# RBR-RAMON.net
KiCad netlist of a schematic drawn in Altium Designer
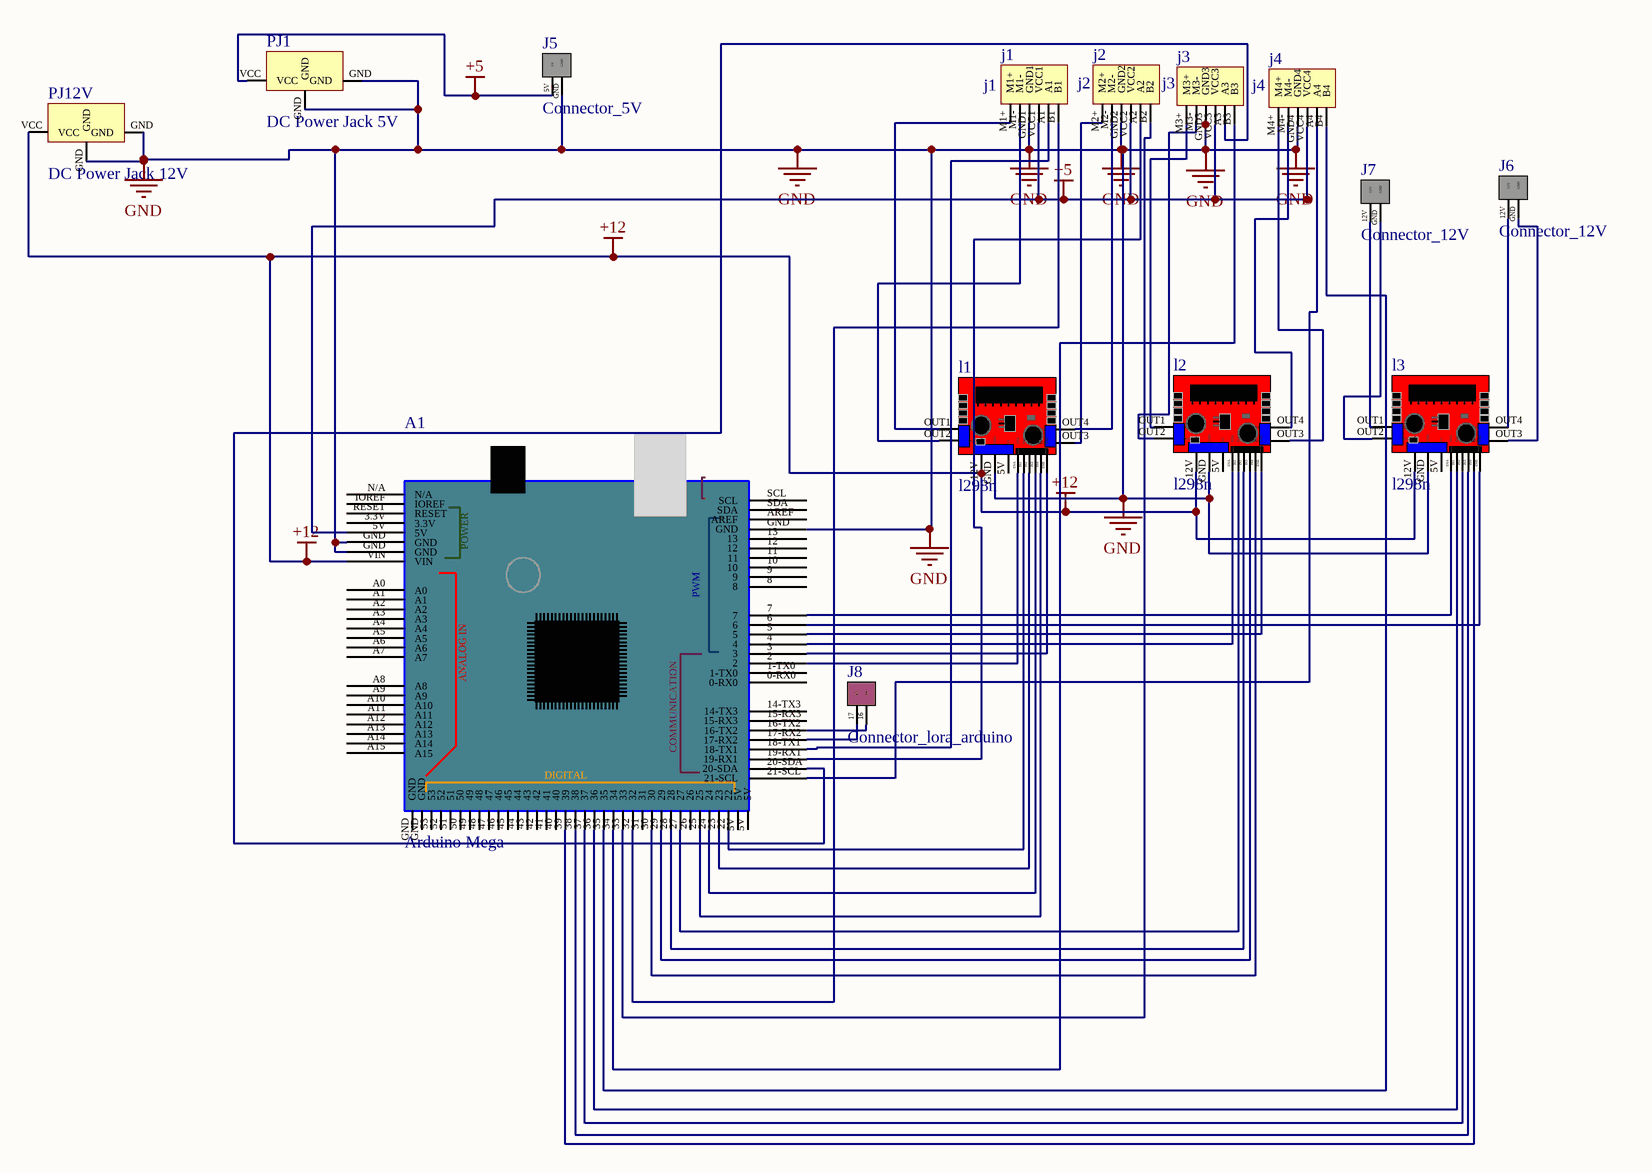
[diagram p0: RBR-RAMON.SchDoc]

(export (version "E")
  (design (tool "Eeschema 10.0.6"))
  (components
    (comp (ref "A1")
      (value "Arduino Mega")
      (footprint "Arduino Mega")
      (libsource (lib "RBR-RAMON") (part "Arduino Mega"))
    )
    (comp (ref "j1")
      (value "j1")
      (footprint "CONECTOR JST M1")
      (libsource (lib "RBR-RAMON") (part "CONECTOR JST M1"))
    )
    (comp (ref "j2")
      (value "j2")
      (footprint "CONECTOR JST M2")
      (libsource (lib "RBR-RAMON") (part "CONECTOR JST M2"))
    )
    (comp (ref "j3")
      (value "j3")
      (footprint "CONECTOR JST M3")
      (libsource (lib "RBR-RAMON") (part "CONECTOR JST M3"))
    )
    (comp (ref "j4")
      (value "j4")
      (footprint "CONECTOR JST M4")
      (libsource (lib "RBR-RAMON") (part "CONECTOR JST M4"))
    )
    (comp (ref "J5")
      (value "Connector_5V")
      (footprint "Conector_5V")
      (libsource (lib "RBR-RAMON") (part "Connector_5V"))
    )
    (comp (ref "J6")
      (value "Connector_12V")
      (footprint "Conector_12V")
      (libsource (lib "RBR-RAMON") (part "Connector_12V"))
    )
    (comp (ref "J7")
      (value "Connector_12V")
      (footprint "Conector_12V")
      (libsource (lib "RBR-RAMON") (part "Connector_12V"))
    )
    (comp (ref "J8")
      (value "Connector_lora_arduino")
      (footprint "Conector_lora_arduino")
      (libsource (lib "RBR-RAMON") (part "Connector_lora_arduino"))
    )
    (comp (ref "l1")
      (value "l298n")
      (footprint "L298N_Conectores")
      (libsource (lib "RBR-RAMON") (part "l298n"))
    )
    (comp (ref "l2")
      (value "l298n")
      (footprint "L298N_Conectores")
      (libsource (lib "RBR-RAMON") (part "l298n"))
    )
    (comp (ref "l3")
      (value "l298n")
      (footprint "L298N_Conectores")
      (libsource (lib "RBR-RAMON") (part "l298n"))
    )
    (comp (ref "PJ1")
      (value "DC Power Jack 5V")
      (footprint "DC Power Jack5V")
      (libsource (lib "RBR-RAMON") (part "DC Power Jack 5V"))
    )
    (comp (ref "PJ12V")
      (value "DC Power Jack 12V")
      (footprint "DC Power Jack12V")
      (libsource (lib "RBR-RAMON") (part "DC Power Jack 12V"))
    )
  )
  (nets
    (net (code "1") (name "+5") (class "Default")
      (node (ref "A1") (pin "5V") (pinfunction "5V_5V") (pintype "passive"))
      (node (ref "J5") (pin "5V") (pinfunction "5V_5V") (pintype "passive"))
      (node (ref "PJ1") (pin "VCC") (pinfunction "VCC_VCC") (pintype "passive"))
      (node (ref "j1") (pin "VCC1") (pinfunction "VCC1_VCC1") (pintype "passive"))
      (node (ref "j2") (pin "VCC2") (pinfunction "VCC2_VCC2") (pintype "passive"))
      (node (ref "j3") (pin "VCC3") (pinfunction "VCC3_VCC3") (pintype "passive"))
      (node (ref "j4") (pin "VCC4") (pinfunction "VCC4_VCC4") (pintype "passive"))
    )
    (net (code "2") (name "+12") (class "Default")
      (node (ref "A1") (pin "VIN") (pinfunction "VIN_VIN") (pintype "passive"))
      (node (ref "PJ12V") (pin "VCC") (pinfunction "VCC_VCC") (pintype "passive"))
      (node (ref "l1") (pin "12V") (pinfunction "12V_12V") (pintype "passive"))
      (node (ref "l2") (pin "12V") (pinfunction "12V_12V") (pintype "passive"))
      (node (ref "l3") (pin "12V") (pinfunction "12V_12V") (pintype "passive"))
    )
    (net (code "3") (name "GND") (class "Default")
      (node (ref "A1") (pin "GND") (pinfunction "GND_GND") (pintype "passive"))
      (node (ref "J5") (pin "GND") (pinfunction "GND_GND") (pintype "passive"))
      (node (ref "PJ1") (pin "GND") (pinfunction "GND_GND") (pintype "passive"))
      (node (ref "PJ12V") (pin "GND") (pinfunction "GND_GND") (pintype "passive"))
      (node (ref "j1") (pin "GND1") (pinfunction "GND1_GND1") (pintype "passive"))
      (node (ref "j2") (pin "GND2") (pinfunction "GND2_GND2") (pintype "passive"))
      (node (ref "j3") (pin "GND3") (pinfunction "GND3_GND3") (pintype "passive"))
      (node (ref "j4") (pin "GND4") (pinfunction "GND4_GND4") (pintype "passive"))
      (node (ref "l1") (pin "GND") (pinfunction "GND_GND") (pintype "passive"))
      (node (ref "l2") (pin "GND") (pinfunction "GND_GND") (pintype "passive"))
      (node (ref "l3") (pin "GND") (pinfunction "GND_GND") (pintype "passive"))
    )
    (net (code "4") (name "Net-(A1-Pad3)") (class "Default")
      (node (ref "A1") (pin "3") (pinfunction "3_3") (pintype "passive"))
      (node (ref "l1") (pin "ENB") (pinfunction "ENB_ENB") (pintype "passive"))
    )
    (net (code "5") (name "Net-(A1-Pad5)") (class "Default")
      (node (ref "A1") (pin "5") (pinfunction "5_5") (pintype "passive"))
      (node (ref "l2") (pin "ENB") (pinfunction "ENB_ENB") (pintype "passive"))
    )
    (net (code "6") (name "Net-(A1-Pad6)") (class "Default")
      (node (ref "A1") (pin "6") (pinfunction "6_6") (pintype "passive"))
      (node (ref "l3") (pin "ENB") (pinfunction "ENB_ENB") (pintype "passive"))
    )
    (net (code "7") (name "Net-(A1-Pad16-TX2)") (class "Default")
      (node (ref "A1") (pin "16-TX2") (pinfunction "16-TX2_16-TX2") (pintype "passive"))
      (node (ref "J8") (pin "16") (pinfunction "16_16") (pintype "passive"))
    )
    (net (code "8") (name "Net-(A1-Pad17-RX2)") (class "Default")
      (node (ref "A1") (pin "17-RX2") (pinfunction "17-RX2_17-RX2") (pintype "passive"))
      (node (ref "J8") (pin "17") (pinfunction "17_17") (pintype "passive"))
    )
    (net (code "9") (name "Net-(A1-Pad18-TX1)") (class "Default")
      (node (ref "A1") (pin "18-TX1") (pinfunction "18-TX1_18-TX1") (pintype "passive"))
      (node (ref "j1") (pin "A1") (pinfunction "A1_A1") (pintype "passive"))
    )
    (net (code "10") (name "Net-(A1-Pad19-RX1)") (class "Default")
      (node (ref "A1") (pin "19-RX1") (pinfunction "19-RX1_19-RX1") (pintype "passive"))
      (node (ref "j2") (pin "A2") (pinfunction "A2_A2") (pintype "passive"))
    )
    (net (code "11") (name "Net-(A1-Pad20-SDA)") (class "Default")
      (node (ref "A1") (pin "20-SDA") (pinfunction "20-SDA_20-SDA") (pintype "passive"))
      (node (ref "j3") (pin "A3") (pinfunction "A3_A3") (pintype "passive"))
    )
    (net (code "12") (name "Net-(A1-Pad21-SCL)") (class "Default")
      (node (ref "A1") (pin "21-SCL") (pinfunction "21-SCL_21-SCL") (pintype "passive"))
      (node (ref "j4") (pin "A4") (pinfunction "A4_A4") (pintype "passive"))
    )
    (net (code "13") (name "Net-(A1-Pad22)") (class "Default")
      (node (ref "A1") (pin "22") (pinfunction "22_22") (pintype "passive"))
      (node (ref "l1") (pin "IN1") (pinfunction "IN1_IN1") (pintype "passive"))
    )
    (net (code "14") (name "Net-(A1-Pad23)") (class "Default")
      (node (ref "A1") (pin "23") (pinfunction "23_23") (pintype "passive"))
      (node (ref "l1") (pin "IN2") (pinfunction "IN2_IN2") (pintype "passive"))
    )
    (net (code "15") (name "Net-(A1-Pad24)") (class "Default")
      (node (ref "A1") (pin "24") (pinfunction "24_24") (pintype "passive"))
      (node (ref "l1") (pin "IN3") (pinfunction "IN3_IN3") (pintype "passive"))
    )
    (net (code "16") (name "Net-(A1-Pad25)") (class "Default")
      (node (ref "A1") (pin "25") (pinfunction "25_25") (pintype "passive"))
      (node (ref "l1") (pin "IN4") (pinfunction "IN4_IN4") (pintype "passive"))
    )
    (net (code "17") (name "Net-(A1-Pad27)") (class "Default")
      (node (ref "A1") (pin "27") (pinfunction "27_27") (pintype "passive"))
      (node (ref "l2") (pin "IN1") (pinfunction "IN1_IN1") (pintype "passive"))
    )
    (net (code "18") (name "Net-(A1-Pad28)") (class "Default")
      (node (ref "A1") (pin "28") (pinfunction "28_28") (pintype "passive"))
      (node (ref "l2") (pin "IN2") (pinfunction "IN2_IN2") (pintype "passive"))
    )
    (net (code "19") (name "Net-(A1-Pad29)") (class "Default")
      (node (ref "A1") (pin "29") (pinfunction "29_29") (pintype "passive"))
      (node (ref "l2") (pin "IN3") (pinfunction "IN3_IN3") (pintype "passive"))
    )
    (net (code "20") (name "Net-(A1-Pad30)") (class "Default")
      (node (ref "A1") (pin "30") (pinfunction "30_30") (pintype "passive"))
      (node (ref "l2") (pin "IN4") (pinfunction "IN4_IN4") (pintype "passive"))
    )
    (net (code "21") (name "Net-(A1-Pad32)") (class "Default")
      (node (ref "A1") (pin "32") (pinfunction "32_32") (pintype "passive"))
      (node (ref "j1") (pin "B1") (pinfunction "B1_B1") (pintype "passive"))
    )
    (net (code "22") (name "Net-(A1-Pad33)") (class "Default")
      (node (ref "A1") (pin "33") (pinfunction "33_33") (pintype "passive"))
      (node (ref "j2") (pin "B2") (pinfunction "B2_B2") (pintype "passive"))
    )
    (net (code "23") (name "Net-(A1-Pad34)") (class "Default")
      (node (ref "A1") (pin "34") (pinfunction "34_34") (pintype "passive"))
      (node (ref "j3") (pin "B3") (pinfunction "B3_B3") (pintype "passive"))
    )
    (net (code "24") (name "Net-(A1-Pad35)") (class "Default")
      (node (ref "A1") (pin "35") (pinfunction "35_35") (pintype "passive"))
      (node (ref "j4") (pin "B4") (pinfunction "B4_B4") (pintype "passive"))
    )
    (net (code "25") (name "Net-(A1-Pad36)") (class "Default")
      (node (ref "A1") (pin "36") (pinfunction "36_36") (pintype "passive"))
      (node (ref "l3") (pin "IN1") (pinfunction "IN1_IN1") (pintype "passive"))
    )
    (net (code "26") (name "Net-(A1-Pad37)") (class "Default")
      (node (ref "A1") (pin "37") (pinfunction "37_37") (pintype "passive"))
      (node (ref "l3") (pin "IN2") (pinfunction "IN2_IN2") (pintype "passive"))
    )
    (net (code "27") (name "Net-(A1-Pad38)") (class "Default")
      (node (ref "A1") (pin "38") (pinfunction "38_38") (pintype "passive"))
      (node (ref "l3") (pin "IN3") (pinfunction "IN3_IN3") (pintype "passive"))
    )
    (net (code "28") (name "Net-(A1-Pad39)") (class "Default")
      (node (ref "A1") (pin "39") (pinfunction "39_39") (pintype "passive"))
      (node (ref "l3") (pin "IN4") (pinfunction "IN4_IN4") (pintype "passive"))
    )
    (net (code "29") (name "Net-(J6-Pad12V)") (class "Default")
      (node (ref "J6") (pin "12V") (pinfunction "12V_12V") (pintype "passive"))
      (node (ref "l3") (pin "OUT4") (pinfunction "OUT4_OUT4") (pintype "passive"))
    )
    (net (code "30") (name "Net-(J6-PadGND)") (class "Default")
      (node (ref "J6") (pin "GND") (pinfunction "GND_GND") (pintype "passive"))
      (node (ref "l3") (pin "OUT3") (pinfunction "OUT3_OUT3") (pintype "passive"))
    )
    (net (code "31") (name "Net-(J7-Pad12V)") (class "Default")
      (node (ref "J7") (pin "12V") (pinfunction "12V_12V") (pintype "passive"))
      (node (ref "l3") (pin "OUT1") (pinfunction "OUT1_OUT1") (pintype "passive"))
    )
    (net (code "32") (name "Net-(J7-PadGND)") (class "Default")
      (node (ref "J7") (pin "GND") (pinfunction "GND_GND") (pintype "passive"))
      (node (ref "l3") (pin "OUT2") (pinfunction "OUT2_OUT2") (pintype "passive"))
    )
    (net (code "33") (name "Net-(j1-PadM1+)") (class "Default")
      (node (ref "j1") (pin "M1+") (pinfunction "M1+_M1+") (pintype "passive"))
      (node (ref "l1") (pin "OUT1") (pinfunction "OUT1_OUT1") (pintype "passive"))
    )
    (net (code "34") (name "Net-(j1-PadM1-)") (class "Default")
      (node (ref "j1") (pin "M1-") (pinfunction "M1-_M1-") (pintype "passive"))
      (node (ref "l1") (pin "OUT2") (pinfunction "OUT2_OUT2") (pintype "passive"))
    )
    (net (code "35") (name "Net-(j2-PadM2+)") (class "Default")
      (node (ref "j2") (pin "M2+") (pinfunction "M2+_M2+") (pintype "passive"))
      (node (ref "l1") (pin "OUT3") (pinfunction "OUT3_OUT3") (pintype "passive"))
    )
    (net (code "36") (name "Net-(j2-PadM2-)") (class "Default")
      (node (ref "j2") (pin "M2-") (pinfunction "M2-_M2-") (pintype "passive"))
      (node (ref "l1") (pin "OUT4") (pinfunction "OUT4_OUT4") (pintype "passive"))
    )
    (net (code "37") (name "Net-(j3-PadM3+)") (class "Default")
      (node (ref "j3") (pin "M3+") (pinfunction "M3+_M3+") (pintype "passive"))
      (node (ref "l2") (pin "OUT1") (pinfunction "OUT1_OUT1") (pintype "passive"))
    )
    (net (code "38") (name "Net-(j3-PadM3-)") (class "Default")
      (node (ref "j3") (pin "M3-") (pinfunction "M3-_M3-") (pintype "passive"))
      (node (ref "l2") (pin "OUT2") (pinfunction "OUT2_OUT2") (pintype "passive"))
    )
    (net (code "39") (name "Net-(j4-PadM4+)") (class "Default")
      (node (ref "j4") (pin "M4+") (pinfunction "M4+_M4+") (pintype "passive"))
      (node (ref "l2") (pin "OUT3") (pinfunction "OUT3_OUT3") (pintype "passive"))
    )
    (net (code "40") (name "Net-(j4-PadM4-)") (class "Default")
      (node (ref "j4") (pin "M4-") (pinfunction "M4-_M4-") (pintype "passive"))
      (node (ref "l2") (pin "OUT4") (pinfunction "OUT4_OUT4") (pintype "passive"))
    )
    (net (code "41") (name "Net-(l1-SDA)") (class "Default")
      (node (ref "A1") (pin "2") (pinfunction "2_2") (pintype "passive"))
      (node (ref "l1") (pin "ENA") (pinfunction "SDA_ENA") (pintype "passive"))
    )
    (net (code "42") (name "Net-(l2-SDA)") (class "Default")
      (node (ref "A1") (pin "4") (pinfunction "4_4") (pintype "passive"))
      (node (ref "l2") (pin "ENA") (pinfunction "SDA_ENA") (pintype "passive"))
    )
    (net (code "43") (name "Net-(l3-SDA)") (class "Default")
      (node (ref "A1") (pin "7") (pinfunction "7_7") (pintype "passive"))
      (node (ref "l3") (pin "ENA") (pinfunction "SDA_ENA") (pintype "passive"))
    )
    (net (code "44") (name "unconnected-(A1-Pad0-RX0)") (class "Default")
      (node (ref "A1") (pin "0-RX0") (pinfunction "0-RX0_0-RX0") (pintype "passive"))
    )
    (net (code "45") (name "unconnected-(A1-Pad1-TX0)") (class "Default")
      (node (ref "A1") (pin "1-TX0") (pinfunction "1-TX0_1-TX0") (pintype "passive"))
    )
    (net (code "46") (name "unconnected-(A1-Pad3.3V)") (class "Default")
      (node (ref "A1") (pin "3.3V") (pinfunction "3.3V_3.3V") (pintype "passive"))
    )
    (net (code "47") (name "unconnected-(A1-Pad5V)") (class "Default")
      (node (ref "A1") (pin "5V") (pinfunction "5V_5V") (pintype "passive"))
    )
    (net (code "48") (name "unconnected-(A1-Pad5V)_1") (class "Default")
      (node (ref "A1") (pin "5V") (pinfunction "5V_5V") (pintype "passive"))
    )
    (net (code "49") (name "unconnected-(A1-Pad8)") (class "Default")
      (node (ref "A1") (pin "8") (pinfunction "8_8") (pintype "passive"))
    )
    (net (code "50") (name "unconnected-(A1-Pad9)") (class "Default")
      (node (ref "A1") (pin "9") (pinfunction "9_9") (pintype "passive"))
    )
    (net (code "51") (name "unconnected-(A1-Pad10)") (class "Default")
      (node (ref "A1") (pin "10") (pinfunction "10_10") (pintype "passive"))
    )
    (net (code "52") (name "unconnected-(A1-Pad11)") (class "Default")
      (node (ref "A1") (pin "11") (pinfunction "11_11") (pintype "passive"))
    )
    (net (code "53") (name "unconnected-(A1-Pad12)") (class "Default")
      (node (ref "A1") (pin "12") (pinfunction "12_12") (pintype "passive"))
    )
    (net (code "54") (name "unconnected-(A1-Pad13)") (class "Default")
      (node (ref "A1") (pin "13") (pinfunction "13_13") (pintype "passive"))
    )
    (net (code "55") (name "unconnected-(A1-Pad14-TX3)") (class "Default")
      (node (ref "A1") (pin "14-TX3") (pinfunction "14-TX3_14-TX3") (pintype "passive"))
    )
    (net (code "56") (name "unconnected-(A1-Pad15-RX3)") (class "Default")
      (node (ref "A1") (pin "15-RX3") (pinfunction "15-RX3_15-RX3") (pintype "passive"))
    )
    (net (code "57") (name "unconnected-(A1-Pad26)") (class "Default")
      (node (ref "A1") (pin "26") (pinfunction "26_26") (pintype "passive"))
    )
    (net (code "58") (name "unconnected-(A1-Pad31)") (class "Default")
      (node (ref "A1") (pin "31") (pinfunction "31_31") (pintype "passive"))
    )
    (net (code "59") (name "unconnected-(A1-Pad40)") (class "Default")
      (node (ref "A1") (pin "40") (pinfunction "40_40") (pintype "passive"))
    )
    (net (code "60") (name "unconnected-(A1-Pad41)") (class "Default")
      (node (ref "A1") (pin "41") (pinfunction "41_41") (pintype "passive"))
    )
    (net (code "61") (name "unconnected-(A1-Pad42)") (class "Default")
      (node (ref "A1") (pin "42") (pinfunction "42_42") (pintype "passive"))
    )
    (net (code "62") (name "unconnected-(A1-Pad43)") (class "Default")
      (node (ref "A1") (pin "43") (pinfunction "43_43") (pintype "passive"))
    )
    (net (code "63") (name "unconnected-(A1-Pad44)") (class "Default")
      (node (ref "A1") (pin "44") (pinfunction "44_44") (pintype "passive"))
    )
    (net (code "64") (name "unconnected-(A1-Pad45)") (class "Default")
      (node (ref "A1") (pin "45") (pinfunction "45_45") (pintype "passive"))
    )
    (net (code "65") (name "unconnected-(A1-Pad46)") (class "Default")
      (node (ref "A1") (pin "46") (pinfunction "46_46") (pintype "passive"))
    )
    (net (code "66") (name "unconnected-(A1-Pad47)") (class "Default")
      (node (ref "A1") (pin "47") (pinfunction "47_47") (pintype "passive"))
    )
    (net (code "67") (name "unconnected-(A1-Pad48)") (class "Default")
      (node (ref "A1") (pin "48") (pinfunction "48_48") (pintype "passive"))
    )
    (net (code "68") (name "unconnected-(A1-Pad49)") (class "Default")
      (node (ref "A1") (pin "49") (pinfunction "49_49") (pintype "passive"))
    )
    (net (code "69") (name "unconnected-(A1-Pad50)") (class "Default")
      (node (ref "A1") (pin "50") (pinfunction "50_50") (pintype "passive"))
    )
    (net (code "70") (name "unconnected-(A1-Pad51)") (class "Default")
      (node (ref "A1") (pin "51") (pinfunction "51_51") (pintype "passive"))
    )
    (net (code "71") (name "unconnected-(A1-Pad52)") (class "Default")
      (node (ref "A1") (pin "52") (pinfunction "52_52") (pintype "passive"))
    )
    (net (code "72") (name "unconnected-(A1-Pad53)") (class "Default")
      (node (ref "A1") (pin "53") (pinfunction "53_53") (pintype "passive"))
    )
    (net (code "73") (name "unconnected-(A1-PadA0)") (class "Default")
      (node (ref "A1") (pin "A0") (pinfunction "A0_A0") (pintype "passive"))
    )
    (net (code "74") (name "unconnected-(A1-PadA1)") (class "Default")
      (node (ref "A1") (pin "A1") (pinfunction "A1_A1") (pintype "passive"))
    )
    (net (code "75") (name "unconnected-(A1-PadA2)") (class "Default")
      (node (ref "A1") (pin "A2") (pinfunction "A2_A2") (pintype "passive"))
    )
    (net (code "76") (name "unconnected-(A1-PadA3)") (class "Default")
      (node (ref "A1") (pin "A3") (pinfunction "A3_A3") (pintype "passive"))
    )
    (net (code "77") (name "unconnected-(A1-PadA4)") (class "Default")
      (node (ref "A1") (pin "A4") (pinfunction "A4_A4") (pintype "passive"))
    )
    (net (code "78") (name "unconnected-(A1-PadA5)") (class "Default")
      (node (ref "A1") (pin "A5") (pinfunction "A5_A5") (pintype "passive"))
    )
    (net (code "79") (name "unconnected-(A1-PadA6)") (class "Default")
      (node (ref "A1") (pin "A6") (pinfunction "A6_A6") (pintype "passive"))
    )
    (net (code "80") (name "unconnected-(A1-PadA7)") (class "Default")
      (node (ref "A1") (pin "A7") (pinfunction "A7_A7") (pintype "passive"))
    )
    (net (code "81") (name "unconnected-(A1-PadA8)") (class "Default")
      (node (ref "A1") (pin "A8") (pinfunction "A8_A8") (pintype "passive"))
    )
    (net (code "82") (name "unconnected-(A1-PadA9)") (class "Default")
      (node (ref "A1") (pin "A9") (pinfunction "A9_A9") (pintype "passive"))
    )
    (net (code "83") (name "unconnected-(A1-PadA10)") (class "Default")
      (node (ref "A1") (pin "A10") (pinfunction "A10_A10") (pintype "passive"))
    )
    (net (code "84") (name "unconnected-(A1-PadA11)") (class "Default")
      (node (ref "A1") (pin "A11") (pinfunction "A11_A11") (pintype "passive"))
    )
    (net (code "85") (name "unconnected-(A1-PadA12)") (class "Default")
      (node (ref "A1") (pin "A12") (pinfunction "A12_A12") (pintype "passive"))
    )
    (net (code "86") (name "unconnected-(A1-PadA13)") (class "Default")
      (node (ref "A1") (pin "A13") (pinfunction "A13_A13") (pintype "passive"))
    )
    (net (code "87") (name "unconnected-(A1-PadA14)") (class "Default")
      (node (ref "A1") (pin "A14") (pinfunction "A14_A14") (pintype "passive"))
    )
    (net (code "88") (name "unconnected-(A1-PadA15)") (class "Default")
      (node (ref "A1") (pin "A15") (pinfunction "A15_A15") (pintype "passive"))
    )
    (net (code "89") (name "unconnected-(A1-PadAREF)") (class "Default")
      (node (ref "A1") (pin "AREF") (pinfunction "AREF_AREF") (pintype "passive"))
    )
    (net (code "90") (name "unconnected-(A1-PadGND)") (class "Default")
      (node (ref "A1") (pin "GND") (pinfunction "GND_GND") (pintype "passive"))
    )
    (net (code "91") (name "unconnected-(A1-PadGND)_1") (class "Default")
      (node (ref "A1") (pin "GND") (pinfunction "GND_GND") (pintype "passive"))
    )
    (net (code "92") (name "unconnected-(A1-PadIOREF)") (class "Default")
      (node (ref "A1") (pin "IOREF") (pinfunction "IOREF_IOREF") (pintype "passive"))
    )
    (net (code "93") (name "unconnected-(A1-PadN{slash}A)") (class "Default")
      (node (ref "A1") (pin "N/A") (pinfunction "N/A_N/A") (pintype "passive"))
    )
    (net (code "94") (name "unconnected-(A1-PadRESET)") (class "Default")
      (node (ref "A1") (pin "RESET") (pinfunction "RESET_RESET") (pintype "passive"))
    )
    (net (code "95") (name "unconnected-(A1-PadSCL)") (class "Default")
      (node (ref "A1") (pin "SCL") (pinfunction "SCL_SCL") (pintype "passive"))
    )
    (net (code "96") (name "unconnected-(A1-PadSDA)") (class "Default")
      (node (ref "A1") (pin "SDA") (pinfunction "SDA_SDA") (pintype "passive"))
    )
    (net (code "97") (name "unconnected-(l1-Pad5V)") (class "Default")
      (node (ref "l1") (pin "5V") (pinfunction "5V_5V") (pintype "passive"))
    )
    (net (code "98") (name "unconnected-(l2-Pad5V)") (class "Default")
      (node (ref "l2") (pin "5V") (pinfunction "5V_5V") (pintype "passive"))
    )
    (net (code "99") (name "unconnected-(l3-Pad5V)") (class "Default")
      (node (ref "l3") (pin "5V") (pinfunction "5V_5V") (pintype "passive"))
    )
  )
)
